# 03200904_05.net
KiCad netlist of a schematic drawn in Altium Designer
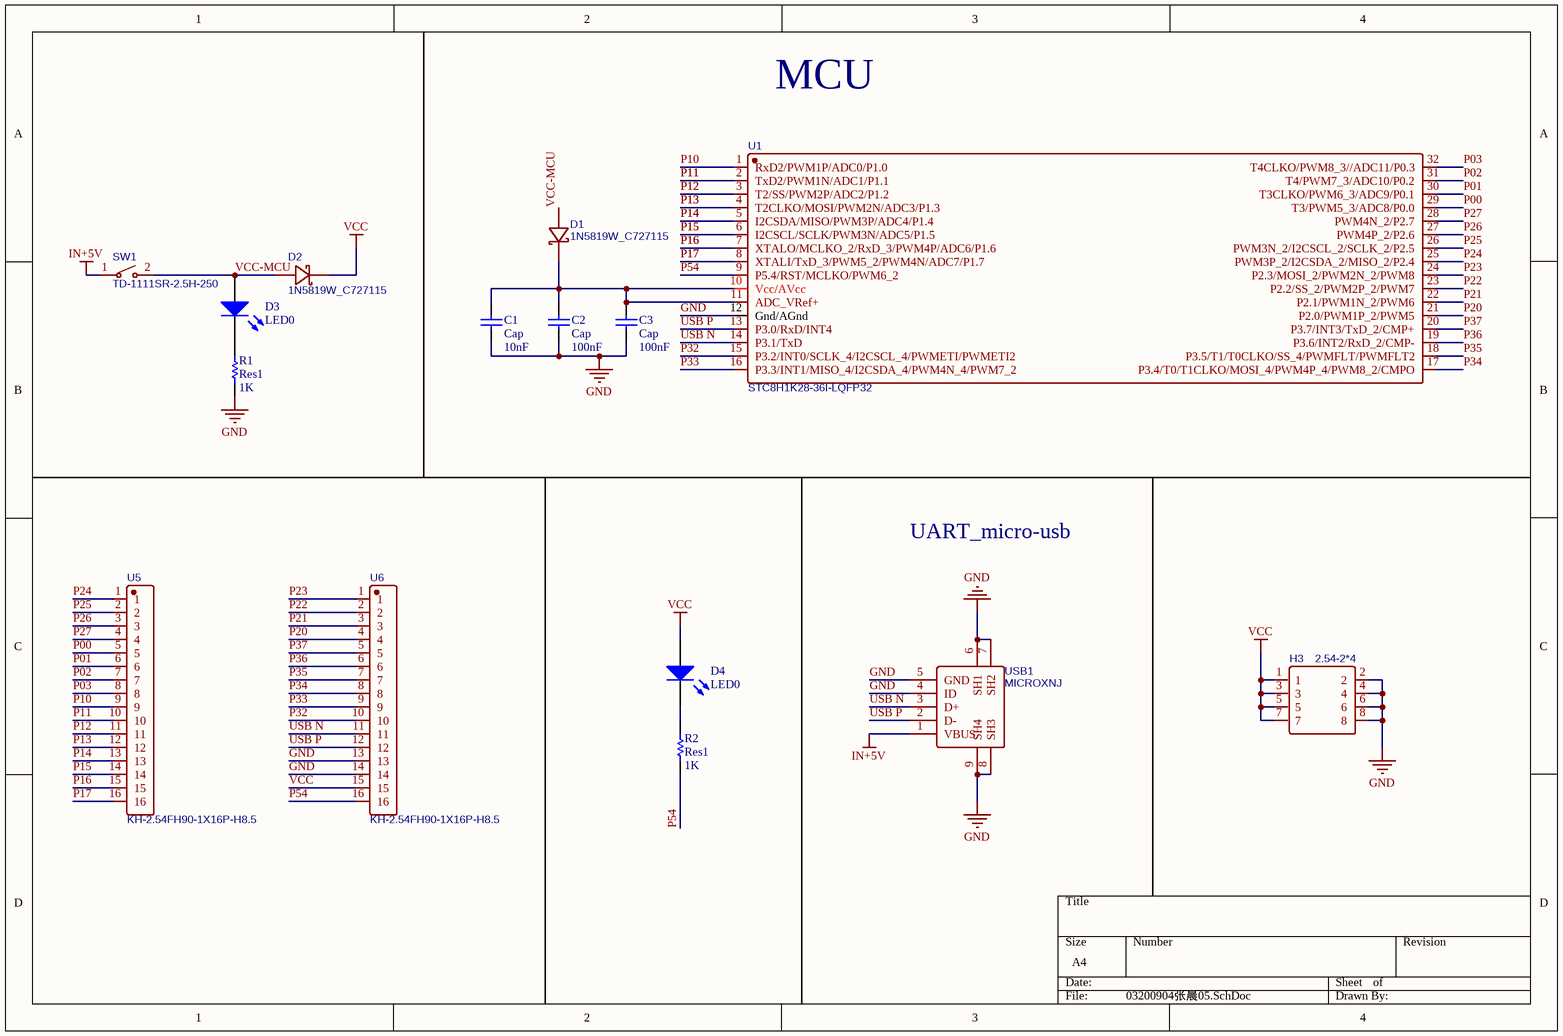
[diagram p0: 03200904张晨05.SchDoc]

(export (version "E")
  (design (tool "Eeschema 10.0.6"))
  (components
    (comp (ref "C1")
      (value "Cap")
      (footprint "C0603")
      (description "Capacitor")
      (fields (field (name "ALTIUM_VALUE") "10nF") (field (name "PUBLISHER") "Altium Limited"))
      (libsource (lib "05") (part "Cap"))
    )
    (comp (ref "C2")
      (value "Cap")
      (footprint "C0603")
      (description "Capacitor")
      (fields (field (name "ALTIUM_VALUE") "100nF") (field (name "PUBLISHER") "Altium Limited"))
      (libsource (lib "05") (part "Cap"))
    )
    (comp (ref "C3")
      (value "Cap")
      (footprint "C0603")
      (description "Capacitor")
      (fields (field (name "ALTIUM_VALUE") "100nF") (field (name "PUBLISHER") "Altium Limited"))
      (libsource (lib "05") (part "Cap"))
    )
    (comp (ref "D1")
      (value "1N5819W_C727115")
      (footprint "SOD-123_L2.8-W1.8-LS3.7-RD")
      (fields
        (field (name "BOM_SUPPLIER PART") "C727115")
        (field (name "BOM_MANUFACTURER PART") "1N5819W")
        (field (name "CONTRIBUTOR") "LCSC")
      )
      (libsource (lib "05") (part "1N5819W_C727115"))
    )
    (comp (ref "D2")
      (value "1N5819W_C727115")
      (footprint "SOD-123_L2.8-W1.8-LS3.7-RD")
      (fields
        (field (name "BOM_SUPPLIER PART") "C727115")
        (field (name "BOM_MANUFACTURER PART") "1N5819W")
        (field (name "CONTRIBUTOR") "LCSC")
      )
      (libsource (lib "05") (part "1N5819W_C727115"))
    )
    (comp (ref "D3")
      (value "LED0")
      (footprint "LED0603")
      (description "Typical INFRARED GaAs LED")
      (fields (field (name "PUBLISHER") "Altium Limited"))
      (libsource (lib "05") (part "LED"))
    )
    (comp (ref "D4")
      (value "LED0")
      (footprint "LED0603")
      (description "Typical INFRARED GaAs LED")
      (fields (field (name "PUBLISHER") "Altium Limited"))
      (libsource (lib "05") (part "LED"))
    )
    (comp (ref "H3")
      (value "2.54-2*4")
      (footprint "HDR-TH_8P-P2.54-V-F-R2-C4-S2.54")
      (fields (field (name "BOM_SUPPLIER PART") "C2977588") (field (name "CONTRIBUTOR") "LCSC"))
      (libsource (lib "05") (part "2.54-2*4"))
    )
    (comp (ref "R1")
      (value "Res1")
      (footprint "R0603")
      (description "Resistor")
      (fields (field (name "ALTIUM_VALUE") "1K") (field (name "PUBLISHER") "Altium Limited"))
      (libsource (lib "05") (part "Res"))
    )
    (comp (ref "R2")
      (value "Res1")
      (footprint "R0603")
      (description "Resistor")
      (fields (field (name "ALTIUM_VALUE") "1K") (field (name "PUBLISHER") "Altium Limited"))
      (libsource (lib "05") (part "Res"))
    )
    (comp (ref "SW1")
      (value "TD-1111SR-2.5H-250")
      (footprint "KEY-SMD_2P-L6.0-W3.6-P7.4-LS8.0-L")
      (fields (field (name "BOM_SUPPLIER PART") "C2905157") (field (name "CONTRIBUTOR") "LCSC"))
      (libsource (lib "05") (part "TD-1111SR-2.5H-250"))
    )
    (comp (ref "U1")
      (value "STC8H1K28-36I-LQFP32")
      (footprint "STC8H1K28I-LQFP-32")
      (fields (field (name "BOM_SUPPLIER PART") "C914618") (field (name "CONTRIBUTOR") "LCSC"))
      (libsource (lib "05") (part "STC8H1K28-36I-LQFP32"))
    )
    (comp (ref "U5")
      (value "KH-2.54FH90-1X16P-H8.5")
      (footprint "HDR-TH_16P-P2.54-V-F-B")
      (fields (field (name "BOM_SUPPLIER PART") "C2932686") (field (name "CONTRIBUTOR") "LCSC"))
      (libsource (lib "05") (part "KH-2.54FH90-1X16P-H8.5"))
    )
    (comp (ref "U6")
      (value "KH-2.54FH90-1X16P-H8.5")
      (footprint "HDR-TH_16P-P2.54-V-F-B")
      (fields (field (name "BOM_SUPPLIER PART") "C2932686") (field (name "CONTRIBUTOR") "LCSC"))
      (libsource (lib "05") (part "KH-2.54FH90-1X16P-H8.5"))
    )
    (comp (ref "USB1")
      (value "MICROXNJ")
      (footprint "MICRO-USB-SMD_MICROXNJ")
      (fields
        (field (name "BOM_SUPPLIER PART") "C404969")
        (field (name "BOM_MANUFACTURER PART") "MicroXNJ")
        (field (name "CONTRIBUTOR") "LCSC")
      )
      (libsource (lib "05") (part "MICROXNJ"))
    )
  )
  (nets
    (net (code "1") (name "/P00") (class "Default")
      (node (ref "U1") (pin "29") (pinfunction "T3/PWM5_3/ADC8/P0.0_29") (pintype "passive"))
      (node (ref "U5") (pin "5") (pinfunction "5_5") (pintype "passive"))
    )
    (net (code "2") (name "/P01") (class "Default")
      (node (ref "U1") (pin "30") (pinfunction "T3CLKO/PWM6_3/ADC9/P0.1_30") (pintype "passive"))
      (node (ref "U5") (pin "6") (pinfunction "6_6") (pintype "passive"))
    )
    (net (code "3") (name "/P02") (class "Default")
      (node (ref "U1") (pin "31") (pinfunction "T4/PWM7_3/ADC10/P0.2_31") (pintype "passive"))
      (node (ref "U5") (pin "7") (pinfunction "7_7") (pintype "passive"))
    )
    (net (code "4") (name "/P03") (class "Default")
      (node (ref "U1") (pin "32") (pinfunction "T4CLKO/PWM8_3//ADC11/P0.3_32") (pintype "passive"))
      (node (ref "U5") (pin "8") (pinfunction "8_8") (pintype "passive"))
    )
    (net (code "5") (name "/P10") (class "Default")
      (node (ref "U1") (pin "1") (pinfunction "RxD2/PWM1P/ADC0/P1.0_1") (pintype "passive"))
      (node (ref "U5") (pin "9") (pinfunction "9_9") (pintype "passive"))
    )
    (net (code "6") (name "/P11") (class "Default")
      (node (ref "U1") (pin "2") (pinfunction "TxD2/PWM1N/ADC1/P1.1_2") (pintype "passive"))
      (node (ref "U5") (pin "10") (pinfunction "10_10") (pintype "passive"))
    )
    (net (code "7") (name "/P12") (class "Default")
      (node (ref "U1") (pin "3") (pinfunction "T2/SS/PWM2P/ADC2/P1.2_3") (pintype "passive"))
      (node (ref "U5") (pin "11") (pinfunction "11_11") (pintype "passive"))
    )
    (net (code "8") (name "/P13") (class "Default")
      (node (ref "U1") (pin "4") (pinfunction "T2CLKO/MOSI/PWM2N/ADC3/P1.3_4") (pintype "passive"))
      (node (ref "U5") (pin "12") (pinfunction "12_12") (pintype "passive"))
    )
    (net (code "9") (name "/P14") (class "Default")
      (node (ref "U1") (pin "5") (pinfunction "I2CSDA/MISO/PWM3P/ADC4/P1.4_5") (pintype "passive"))
      (node (ref "U5") (pin "13") (pinfunction "13_13") (pintype "passive"))
    )
    (net (code "10") (name "/P15") (class "Default")
      (node (ref "U1") (pin "6") (pinfunction "I2CSCL/SCLK/PWM3N/ADC5/P1.5_6") (pintype "passive"))
      (node (ref "U5") (pin "14") (pinfunction "14_14") (pintype "passive"))
    )
    (net (code "11") (name "/P16") (class "Default")
      (node (ref "U1") (pin "7") (pinfunction "XTALO/MCLKO_2/RxD_3/PWM4P/ADC6/P1.6_7") (pintype "passive"))
      (node (ref "U5") (pin "15") (pinfunction "15_15") (pintype "passive"))
    )
    (net (code "12") (name "/P17") (class "Default")
      (node (ref "U1") (pin "8") (pinfunction "XTALI/TxD_3/PWM5_2/PWM4N/ADC7/P1.7_8") (pintype "passive"))
      (node (ref "U5") (pin "16") (pinfunction "16_16") (pintype "passive"))
    )
    (net (code "13") (name "/P20") (class "Default")
      (node (ref "U1") (pin "21") (pinfunction "P2.0/PWM1P_2/PWM5_21") (pintype "passive"))
      (node (ref "U6") (pin "4") (pinfunction "4_4") (pintype "passive"))
    )
    (net (code "14") (name "/P21") (class "Default")
      (node (ref "U1") (pin "22") (pinfunction "P2.1/PWM1N_2/PWM6_22") (pintype "passive"))
      (node (ref "U6") (pin "3") (pinfunction "3_3") (pintype "passive"))
    )
    (net (code "15") (name "/P22") (class "Default")
      (node (ref "U1") (pin "23") (pinfunction "P2.2/SS_2/PWM2P_2/PWM7_23") (pintype "passive"))
      (node (ref "U6") (pin "2") (pinfunction "2_2") (pintype "passive"))
    )
    (net (code "16") (name "/P23") (class "Default")
      (node (ref "U1") (pin "24") (pinfunction "P2.3/MOSI_2/PWM2N_2/PWM8_24") (pintype "passive"))
      (node (ref "U6") (pin "1") (pinfunction "1_1") (pintype "passive"))
    )
    (net (code "17") (name "/P24") (class "Default")
      (node (ref "U1") (pin "25") (pinfunction "PWM3P_2/I2CSDA_2/MISO_2/P2.4_25") (pintype "passive"))
      (node (ref "U5") (pin "1") (pinfunction "1_1") (pintype "passive"))
    )
    (net (code "18") (name "/P25") (class "Default")
      (node (ref "U1") (pin "26") (pinfunction "PWM3N_2/I2CSCL_2/SCLK_2/P2.5_26") (pintype "passive"))
      (node (ref "U5") (pin "2") (pinfunction "2_2") (pintype "passive"))
    )
    (net (code "19") (name "/P26") (class "Default")
      (node (ref "U1") (pin "27") (pinfunction "PWM4P_2/P2.6_27") (pintype "passive"))
      (node (ref "U5") (pin "3") (pinfunction "3_3") (pintype "passive"))
    )
    (net (code "20") (name "/P27") (class "Default")
      (node (ref "U1") (pin "28") (pinfunction "PWM4N_2/P2.7_28") (pintype "passive"))
      (node (ref "U5") (pin "4") (pinfunction "4_4") (pintype "passive"))
    )
    (net (code "21") (name "/P32") (class "Default")
      (node (ref "U1") (pin "15") (pinfunction "P3.2/INT0/SCLK_4/I2CSCL_4/PWMETI/PWMETI2_15") (pintype "passive"))
      (node (ref "U6") (pin "10") (pinfunction "10_10") (pintype "passive"))
    )
    (net (code "22") (name "/P33") (class "Default")
      (node (ref "U1") (pin "16") (pinfunction "P3.3/INT1/MISO_4/I2CSDA_4/PWM4N_4/PWM7_2_16") (pintype "passive"))
      (node (ref "U6") (pin "9") (pinfunction "9_9") (pintype "passive"))
    )
    (net (code "23") (name "/P34") (class "Default")
      (node (ref "U1") (pin "17") (pinfunction "P3.4/T0/T1CLKO/MOSI_4/PWM4P_4/PWM8_2/CMPO_17") (pintype "passive"))
      (node (ref "U6") (pin "8") (pinfunction "8_8") (pintype "passive"))
    )
    (net (code "24") (name "/P35") (class "Default")
      (node (ref "U1") (pin "18") (pinfunction "P3.5/T1/T0CLKO/SS_4/PWMFLT/PWMFLT2_18") (pintype "passive"))
      (node (ref "U6") (pin "7") (pinfunction "7_7") (pintype "passive"))
    )
    (net (code "25") (name "/P36") (class "Default")
      (node (ref "U1") (pin "19") (pinfunction "P3.6/INT2/RxD_2/CMP-_19") (pintype "passive"))
      (node (ref "U6") (pin "6") (pinfunction "6_6") (pintype "passive"))
    )
    (net (code "26") (name "/P37") (class "Default")
      (node (ref "U1") (pin "20") (pinfunction "P3.7/INT3/TxD_2/CMP+_20") (pintype "passive"))
      (node (ref "U6") (pin "5") (pinfunction "5_5") (pintype "passive"))
    )
    (net (code "27") (name "/P54") (class "Default")
      (node (ref "R2") (pin "1") (pinfunction "1_1") (pintype "passive"))
      (node (ref "U1") (pin "9") (pinfunction "P5.4/RST/MCLKO/PWM6_2_9") (pintype "passive"))
      (node (ref "U6") (pin "16") (pinfunction "16_16") (pintype "passive"))
    )
    (net (code "28") (name "/USB N") (class "Default")
      (node (ref "U1") (pin "14") (pinfunction "P3.1/TxD_14") (pintype "passive"))
      (node (ref "U6") (pin "11") (pinfunction "11_11") (pintype "passive"))
      (node (ref "USB1") (pin "3") (pinfunction "D+_3") (pintype "passive"))
    )
    (net (code "29") (name "/USB P") (class "Default")
      (node (ref "U1") (pin "13") (pinfunction "P3.0/RxD/INT4_13") (pintype "passive"))
      (node (ref "U6") (pin "12") (pinfunction "12_12") (pintype "passive"))
      (node (ref "USB1") (pin "2") (pinfunction "D-_2") (pintype "passive"))
    )
    (net (code "30") (name "/VCC-MCU") (class "Default")
      (node (ref "D1") (pin "2") (pinfunction "A_2") (pintype "passive"))
      (node (ref "D2") (pin "2") (pinfunction "A_2") (pintype "passive"))
      (node (ref "D3") (pin "2") (pinfunction "A_2") (pintype "passive"))
      (node (ref "SW1") (pin "2") (pinfunction "2_2") (pintype "passive"))
    )
    (net (code "31") (name "GND") (class "Default")
      (node (ref "C1") (pin "1") (pinfunction "1_1") (pintype "passive"))
      (node (ref "C2") (pin "1") (pinfunction "1_1") (pintype "passive"))
      (node (ref "C3") (pin "1") (pinfunction "1_1") (pintype "passive"))
      (node (ref "H3") (pin "2") (pinfunction "2_2") (pintype "passive"))
      (node (ref "H3") (pin "4") (pinfunction "4_4") (pintype "passive"))
      (node (ref "H3") (pin "6") (pinfunction "6_6") (pintype "passive"))
      (node (ref "H3") (pin "8") (pinfunction "8_8") (pintype "passive"))
      (node (ref "R1") (pin "1") (pinfunction "1_1") (pintype "passive"))
      (node (ref "U1") (pin "12") (pinfunction "Gnd/AGnd_12") (pintype "passive"))
      (node (ref "U6") (pin "13") (pinfunction "13_13") (pintype "passive"))
      (node (ref "U6") (pin "14") (pinfunction "14_14") (pintype "passive"))
      (node (ref "USB1") (pin "4") (pinfunction "ID_4") (pintype "passive"))
      (node (ref "USB1") (pin "5") (pinfunction "GND_5") (pintype "passive"))
      (node (ref "USB1") (pin "6") (pinfunction "SH1_6") (pintype "passive"))
      (node (ref "USB1") (pin "7") (pinfunction "SH2_7") (pintype "passive"))
      (node (ref "USB1") (pin "8") (pinfunction "SH3_8") (pintype "passive"))
      (node (ref "USB1") (pin "9") (pinfunction "SH4_9") (pintype "passive"))
    )
    (net (code "32") (name "IN+5V") (class "Default")
      (node (ref "SW1") (pin "1") (pinfunction "1_1") (pintype "passive"))
      (node (ref "USB1") (pin "1") (pinfunction "VBUS_1") (pintype "passive"))
    )
    (net (code "33") (name "Net-(D1-C)") (class "Default")
      (node (ref "C1") (pin "2") (pinfunction "2_2") (pintype "passive"))
      (node (ref "C2") (pin "2") (pinfunction "2_2") (pintype "passive"))
      (node (ref "C3") (pin "2") (pinfunction "2_2") (pintype "passive"))
      (node (ref "D1") (pin "1") (pinfunction "C_1") (pintype "passive"))
      (node (ref "U1") (pin "10") (pinfunction "Vcc/AVcc_10") (pintype "passive"))
      (node (ref "U1") (pin "11") (pinfunction "ADC_VRef+_11") (pintype "passive"))
    )
    (net (code "34") (name "Net-(D3-K)") (class "Default")
      (node (ref "D3") (pin "1") (pinfunction "K_1") (pintype "passive"))
      (node (ref "R1") (pin "2") (pinfunction "2_2") (pintype "passive"))
    )
    (net (code "35") (name "Net-(D4-K)") (class "Default")
      (node (ref "D4") (pin "1") (pinfunction "K_1") (pintype "passive"))
      (node (ref "R2") (pin "2") (pinfunction "2_2") (pintype "passive"))
    )
    (net (code "36") (name "VCC") (class "Default")
      (node (ref "D2") (pin "1") (pinfunction "C_1") (pintype "passive"))
      (node (ref "D4") (pin "2") (pinfunction "A_2") (pintype "passive"))
      (node (ref "H3") (pin "1") (pinfunction "1_1") (pintype "passive"))
      (node (ref "H3") (pin "3") (pinfunction "3_3") (pintype "passive"))
      (node (ref "H3") (pin "5") (pinfunction "5_5") (pintype "passive"))
      (node (ref "H3") (pin "7") (pinfunction "7_7") (pintype "passive"))
      (node (ref "U6") (pin "15") (pinfunction "15_15") (pintype "passive"))
    )
  )
)
